# main.net
KiCad netlist of a schematic drawn in EAGLE
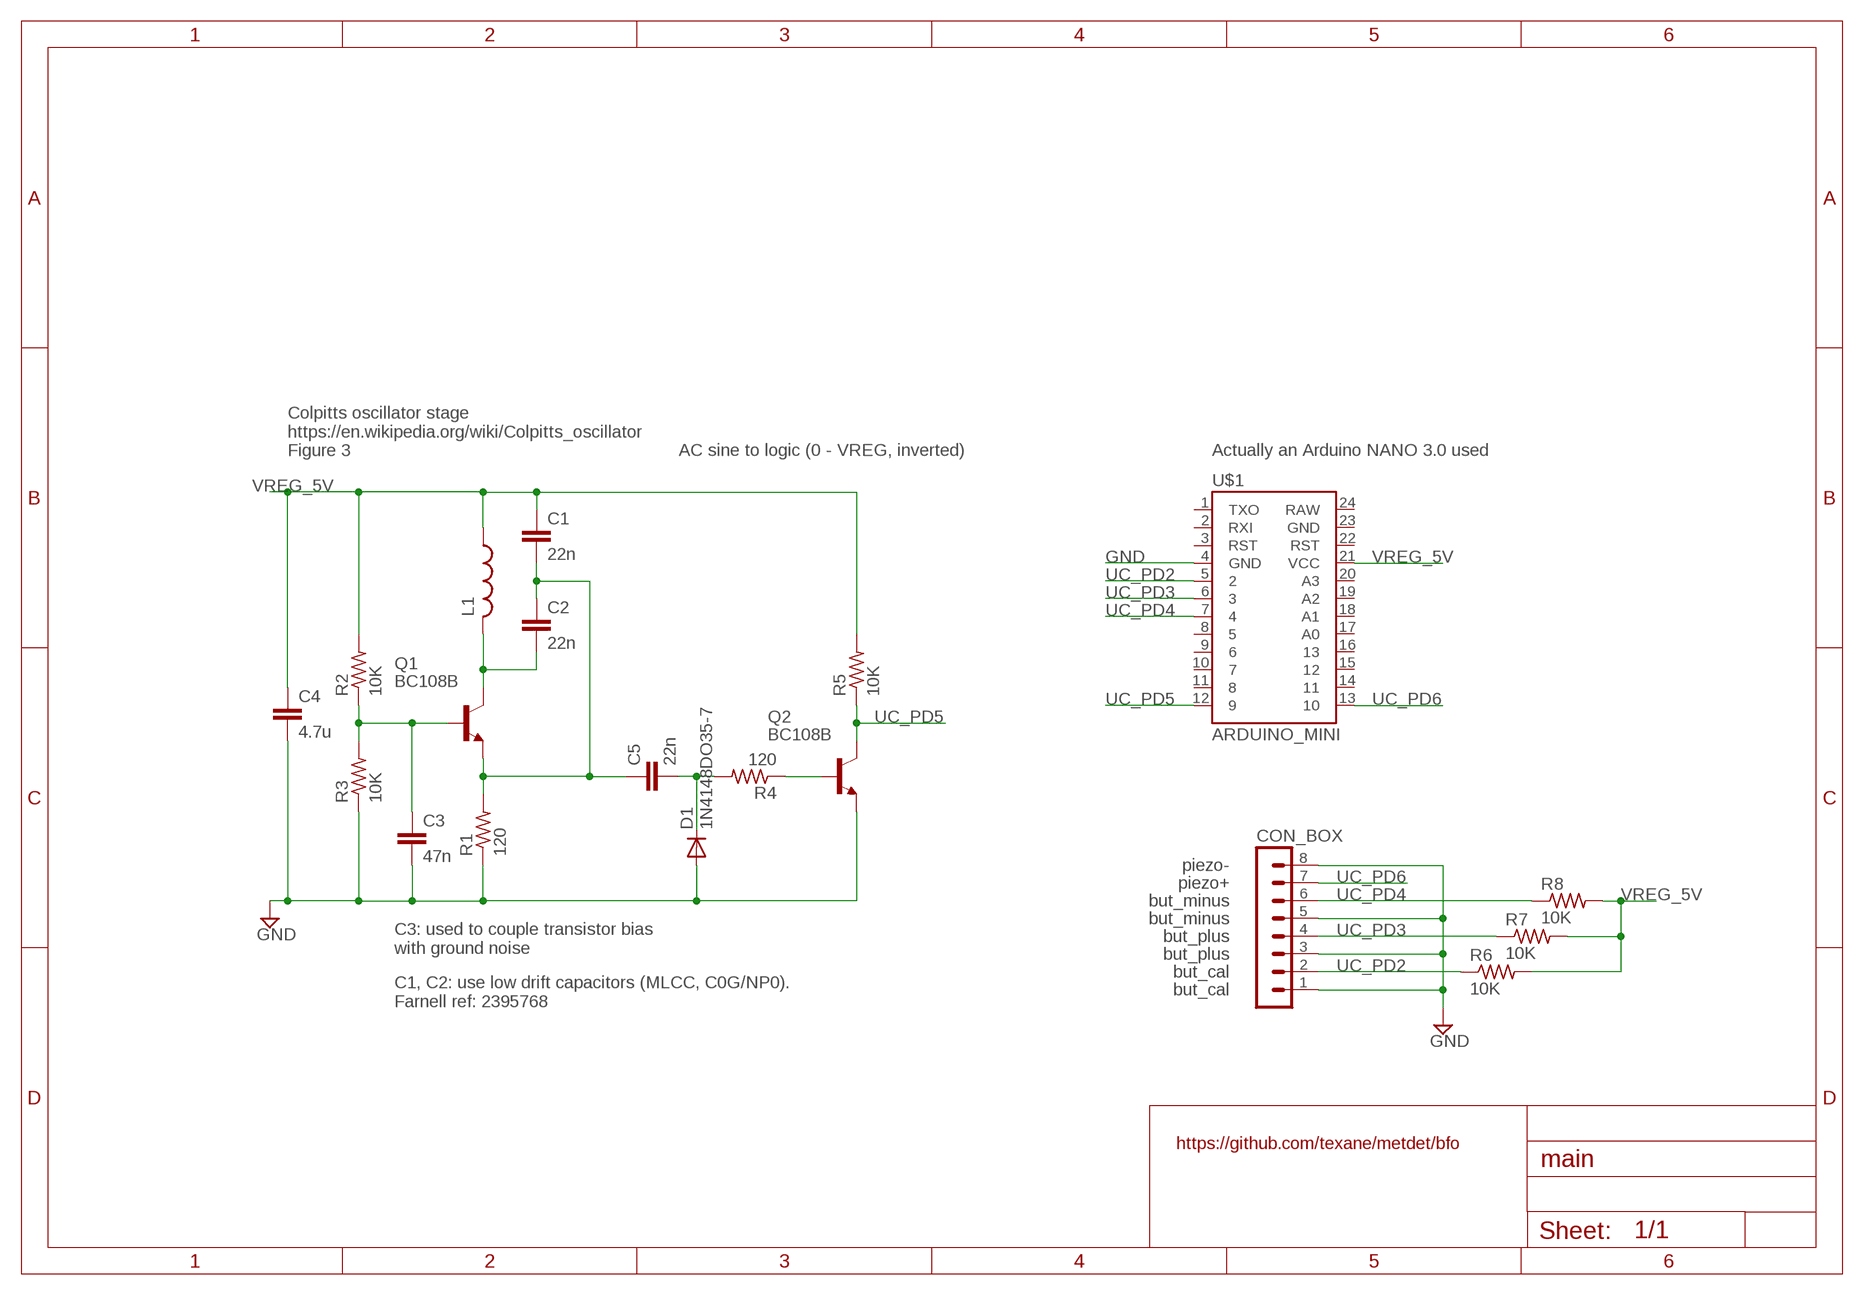
[diagram p0: schematic, sheet 1]

(export (version "E")
  (design (tool "Eeschema 10.0.6"))
  (components
    (comp (ref "C1")
      (value "22n")
      (footprint "eagle-import:C025-024X044")
      (libsource (lib "eagle-import") (part "C-EU025-024X044"))
    )
    (comp (ref "C2")
      (value "22n")
      (footprint "eagle-import:C025-024X044")
      (libsource (lib "eagle-import") (part "C-EU025-024X044"))
    )
    (comp (ref "C3")
      (value "47n")
      (footprint "eagle-import:C025-024X044")
      (libsource (lib "eagle-import") (part "C-EU025-024X044"))
    )
    (comp (ref "C4")
      (value "4.7u")
      (footprint "eagle-import:C025-024X044")
      (libsource (lib "eagle-import") (part "C-EU025-024X044"))
    )
    (comp (ref "C5")
      (value "22n")
      (footprint "eagle-import:C025-024X044")
      (libsource (lib "eagle-import") (part "C-EU025-024X044"))
    )
    (comp (ref "CON_BOX")
      (value "MA08-1")
      (footprint "eagle-import:MA08-1")
      (libsource (lib "eagle-import") (part "MA08-1"))
    )
    (comp (ref "D1")
      (value "1N4148DO35-7")
      (footprint "eagle-import:DO35-7")
      (libsource (lib "eagle-import") (part "1N4148DO35-7"))
    )
    (comp (ref "L1")
      (value "L-US0204/5")
      (footprint "eagle-import:0204_5")
      (libsource (lib "eagle-import") (part "L-US0204/5"))
    )
    (comp (ref "Q1")
      (value "BC108B")
      (footprint "eagle-import:TO18")
      (libsource (lib "eagle-import") (part "BC108B"))
    )
    (comp (ref "Q2")
      (value "BC108B")
      (footprint "eagle-import:TO18")
      (libsource (lib "eagle-import") (part "BC108B"))
    )
    (comp (ref "R1")
      (value "120")
      (footprint "eagle-import:0204V")
      (libsource (lib "eagle-import") (part "R-US_0204/2V"))
    )
    (comp (ref "R2")
      (value "10K")
      (footprint "eagle-import:0204V")
      (libsource (lib "eagle-import") (part "R-US_0204/2V"))
    )
    (comp (ref "R3")
      (value "10K")
      (footprint "eagle-import:0204V")
      (libsource (lib "eagle-import") (part "R-US_0204/2V"))
    )
    (comp (ref "R4")
      (value "120")
      (footprint "eagle-import:0204V")
      (libsource (lib "eagle-import") (part "R-US_0204/2V"))
    )
    (comp (ref "R5")
      (value "10K")
      (footprint "eagle-import:0204V")
      (libsource (lib "eagle-import") (part "R-US_0204/2V"))
    )
    (comp (ref "R6")
      (value "10K")
      (footprint "eagle-import:0204V")
      (libsource (lib "eagle-import") (part "R-US_0204/2V"))
    )
    (comp (ref "R7")
      (value "10K")
      (footprint "eagle-import:0204V")
      (libsource (lib "eagle-import") (part "R-US_0204/2V"))
    )
    (comp (ref "R8")
      (value "10K")
      (footprint "eagle-import:0204V")
      (libsource (lib "eagle-import") (part "R-US_0204/2V"))
    )
    (comp (ref "U$1")
      (value "ARDUINO_MINI")
      (footprint "eagle-import:ARDUINO_MINI")
      (libsource (lib "eagle-import") (part "ARDUINO_MINI"))
    )
  )
  (nets
    (net (code "1") (name "/UC_PD2") (class "Default")
      (node (ref "CON_BOX") (pin "2") (pinfunction "2_2") (pintype "passive"))
      (node (ref "R6") (pin "1") (pinfunction "1_1") (pintype "passive"))
      (node (ref "U$1") (pin "5") (pinfunction "2_5") (pintype "bidirectional"))
    )
    (net (code "2") (name "/UC_PD3") (class "Default")
      (node (ref "CON_BOX") (pin "4") (pinfunction "4_4") (pintype "passive"))
      (node (ref "R7") (pin "1") (pinfunction "1_1") (pintype "passive"))
      (node (ref "U$1") (pin "6") (pinfunction "3_6") (pintype "bidirectional"))
    )
    (net (code "3") (name "/UC_PD4") (class "Default")
      (node (ref "CON_BOX") (pin "6") (pinfunction "6_6") (pintype "passive"))
      (node (ref "R8") (pin "1") (pinfunction "1_1") (pintype "passive"))
      (node (ref "U$1") (pin "7") (pinfunction "4_7") (pintype "bidirectional"))
    )
    (net (code "4") (name "/UC_PD5") (class "Default")
      (node (ref "Q2") (pin "3") (pinfunction "C_3") (pintype "passive"))
      (node (ref "R5") (pin "1") (pinfunction "1_1") (pintype "passive"))
      (node (ref "U$1") (pin "12") (pinfunction "9_12") (pintype "bidirectional"))
    )
    (net (code "5") (name "/UC_PD6") (class "Default")
      (node (ref "CON_BOX") (pin "7") (pinfunction "7_7") (pintype "passive"))
      (node (ref "U$1") (pin "13") (pinfunction "10_13") (pintype "bidirectional"))
    )
    (net (code "6") (name "/VREG_5V") (class "Default")
      (node (ref "C1") (pin "1") (pinfunction "1_1") (pintype "passive"))
      (node (ref "C4") (pin "1") (pinfunction "1_1") (pintype "passive"))
      (node (ref "L1") (pin "1") (pinfunction "1_1") (pintype "passive"))
      (node (ref "R2") (pin "2") (pinfunction "2_2") (pintype "passive"))
      (node (ref "R5") (pin "2") (pinfunction "2_2") (pintype "passive"))
      (node (ref "R6") (pin "2") (pinfunction "2_2") (pintype "passive"))
      (node (ref "R7") (pin "2") (pinfunction "2_2") (pintype "passive"))
      (node (ref "R8") (pin "2") (pinfunction "2_2") (pintype "passive"))
      (node (ref "U$1") (pin "21") (pinfunction "VCC_21") (pintype "bidirectional"))
    )
    (net (code "7") (name "GND") (class "Default")
      (node (ref "C3") (pin "2") (pinfunction "2_2") (pintype "passive"))
      (node (ref "C4") (pin "2") (pinfunction "2_2") (pintype "passive"))
      (node (ref "CON_BOX") (pin "1") (pinfunction "1_1") (pintype "passive"))
      (node (ref "CON_BOX") (pin "3") (pinfunction "3_3") (pintype "passive"))
      (node (ref "CON_BOX") (pin "5") (pinfunction "5_5") (pintype "passive"))
      (node (ref "CON_BOX") (pin "8") (pinfunction "8_8") (pintype "passive"))
      (node (ref "D1") (pin "A") (pinfunction "A_A") (pintype "passive"))
      (node (ref "Q2") (pin "1") (pinfunction "E_1") (pintype "passive"))
      (node (ref "R1") (pin "1") (pinfunction "1_1") (pintype "passive"))
      (node (ref "R3") (pin "1") (pinfunction "1_1") (pintype "passive"))
      (node (ref "U$1") (pin "4") (pinfunction "GND_4") (pintype "bidirectional"))
    )
    (net (code "8") (name "Net-(C5-Pad2)") (class "Default")
      (node (ref "C5") (pin "2") (pinfunction "2_2") (pintype "passive"))
      (node (ref "D1") (pin "C") (pinfunction "C_C") (pintype "passive"))
      (node (ref "R4") (pin "2") (pinfunction "2_2") (pintype "passive"))
    )
    (net (code "9") (name "Net-(Q1-B)") (class "Default")
      (node (ref "C3") (pin "1") (pinfunction "1_1") (pintype "passive"))
      (node (ref "Q1") (pin "2") (pinfunction "B_2") (pintype "passive"))
      (node (ref "R2") (pin "1") (pinfunction "1_1") (pintype "passive"))
      (node (ref "R3") (pin "2") (pinfunction "2_2") (pintype "passive"))
    )
    (net (code "10") (name "Net-(Q1-C)") (class "Default")
      (node (ref "C2") (pin "2") (pinfunction "2_2") (pintype "passive"))
      (node (ref "L1") (pin "2") (pinfunction "2_2") (pintype "passive"))
      (node (ref "Q1") (pin "3") (pinfunction "C_3") (pintype "passive"))
    )
    (net (code "11") (name "Net-(Q1-E)") (class "Default")
      (node (ref "C1") (pin "2") (pinfunction "2_2") (pintype "passive"))
      (node (ref "C2") (pin "1") (pinfunction "1_1") (pintype "passive"))
      (node (ref "C5") (pin "1") (pinfunction "1_1") (pintype "passive"))
      (node (ref "Q1") (pin "1") (pinfunction "E_1") (pintype "passive"))
      (node (ref "R1") (pin "2") (pinfunction "2_2") (pintype "passive"))
    )
    (net (code "12") (name "Net-(Q2-B)") (class "Default")
      (node (ref "Q2") (pin "2") (pinfunction "B_2") (pintype "passive"))
      (node (ref "R4") (pin "1") (pinfunction "1_1") (pintype "passive"))
    )
    (net (code "13") (name "unconnected-(U$1-5-Pad8)") (class "Default")
      (node (ref "U$1") (pin "8") (pinfunction "5_8") (pintype "bidirectional"))
    )
    (net (code "14") (name "unconnected-(U$1-6-Pad9)") (class "Default")
      (node (ref "U$1") (pin "9") (pinfunction "6_9") (pintype "bidirectional"))
    )
    (net (code "15") (name "unconnected-(U$1-7-Pad10)") (class "Default")
      (node (ref "U$1") (pin "10") (pinfunction "7_10") (pintype "bidirectional"))
    )
    (net (code "16") (name "unconnected-(U$1-8-Pad11)") (class "Default")
      (node (ref "U$1") (pin "11") (pinfunction "8_11") (pintype "bidirectional"))
    )
    (net (code "17") (name "unconnected-(U$1-11-Pad14)") (class "Default")
      (node (ref "U$1") (pin "14") (pinfunction "11_14") (pintype "bidirectional"))
    )
    (net (code "18") (name "unconnected-(U$1-12-Pad15)") (class "Default")
      (node (ref "U$1") (pin "15") (pinfunction "12_15") (pintype "bidirectional"))
    )
    (net (code "19") (name "unconnected-(U$1-13-Pad16)") (class "Default")
      (node (ref "U$1") (pin "16") (pinfunction "13_16") (pintype "bidirectional"))
    )
    (net (code "20") (name "unconnected-(U$1-A0-Pad17)") (class "Default")
      (node (ref "U$1") (pin "17") (pinfunction "A0_17") (pintype "bidirectional"))
    )
    (net (code "21") (name "unconnected-(U$1-A1-Pad18)") (class "Default")
      (node (ref "U$1") (pin "18") (pinfunction "A1_18") (pintype "bidirectional"))
    )
    (net (code "22") (name "unconnected-(U$1-A2-Pad19)") (class "Default")
      (node (ref "U$1") (pin "19") (pinfunction "A2_19") (pintype "bidirectional"))
    )
    (net (code "23") (name "unconnected-(U$1-A3-Pad20)") (class "Default")
      (node (ref "U$1") (pin "20") (pinfunction "A3_20") (pintype "bidirectional"))
    )
    (net (code "24") (name "unconnected-(U$1-GND-Pad23)") (class "Default")
      (node (ref "U$1") (pin "23") (pinfunction "GND_23") (pintype "bidirectional"))
    )
    (net (code "25") (name "unconnected-(U$1-RAW-Pad24)") (class "Default")
      (node (ref "U$1") (pin "24") (pinfunction "RAW_24") (pintype "bidirectional"))
    )
    (net (code "26") (name "unconnected-(U$1-RST-Pad3)") (class "Default")
      (node (ref "U$1") (pin "3") (pinfunction "RST_3") (pintype "bidirectional"))
    )
    (net (code "27") (name "unconnected-(U$1-RST-Pad22)") (class "Default")
      (node (ref "U$1") (pin "22") (pinfunction "RST_22") (pintype "bidirectional"))
    )
    (net (code "28") (name "unconnected-(U$1-RXI-Pad2)") (class "Default")
      (node (ref "U$1") (pin "2") (pinfunction "RXI_2") (pintype "bidirectional"))
    )
    (net (code "29") (name "unconnected-(U$1-TXO-Pad1)") (class "Default")
      (node (ref "U$1") (pin "1") (pinfunction "TXO_1") (pintype "bidirectional"))
    )
  )
)
